# 2_SIM.net
KiCad netlist of a schematic drawn in Altium Designer
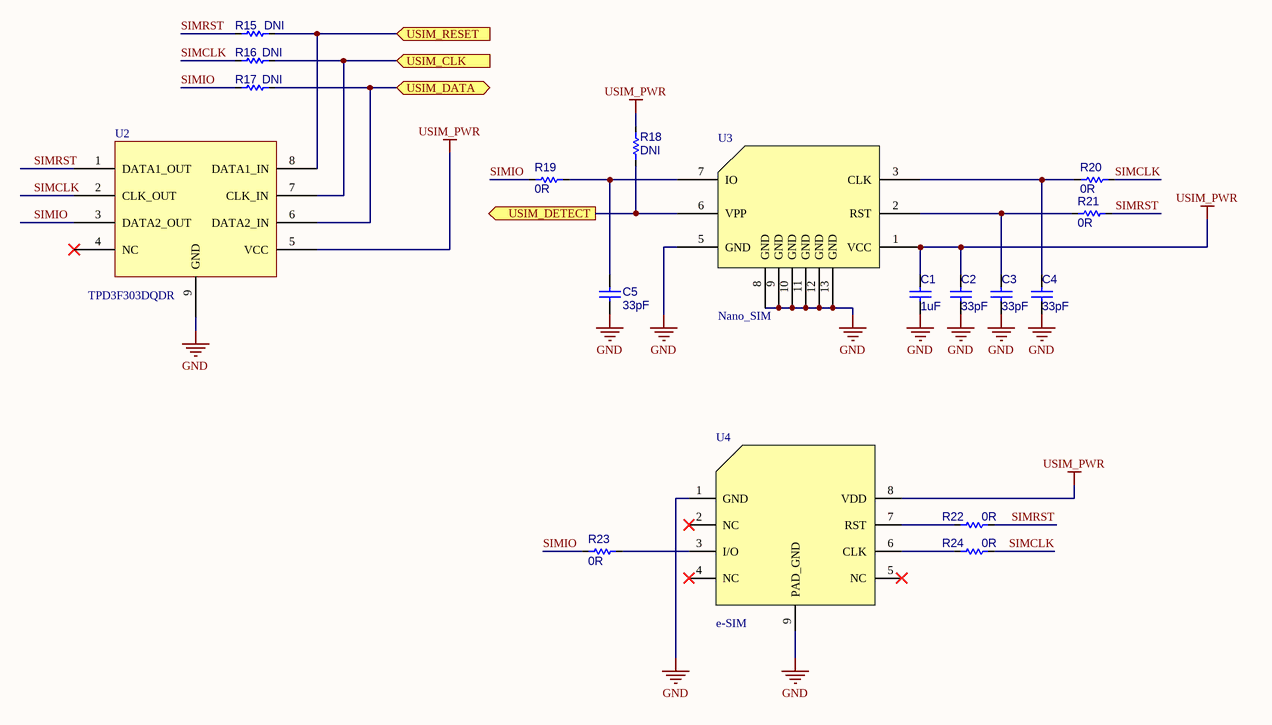
[diagram p0: 2.SIM.SchDoc]

(export (version "E")
  (design (tool "Eeschema 10.0.6"))
  (components
    (comp (ref "C1")
      (value "1uF")
      (footprint "CAP-0402")
      (description "Ceramic CAP 0402(1005)")
      (libsource (lib "Scott_lib") (part "CAP-0402"))
    )
    (comp (ref "C2")
      (value "33pF")
      (footprint "CAP-0402")
      (description "Ceramic CAP 0402(1005)")
      (libsource (lib "Scott_lib") (part "CAP-0402"))
    )
    (comp (ref "C3")
      (value "33pF")
      (footprint "CAP-0402")
      (description "Ceramic CAP 0402(1005)")
      (libsource (lib "Scott_lib") (part "CAP-0402"))
    )
    (comp (ref "C4")
      (value "33pF")
      (footprint "CAP-0402")
      (description "Ceramic CAP 0402(1005)")
      (libsource (lib "Scott_lib") (part "CAP-0402"))
    )
    (comp (ref "C5")
      (value "33pF")
      (footprint "CAP-0402")
      (description "Ceramic CAP 0402(1005)")
      (libsource (lib "Scott_lib") (part "CAP-0402"))
    )
    (comp (ref "R15")
      (value "DNI")
      (footprint "RES-0402")
      (description "RES-0402")
      (libsource (lib "Scott_lib") (part "RES-0402"))
    )
    (comp (ref "R16")
      (value "DNI")
      (footprint "RES-0402")
      (description "RES-0402")
      (libsource (lib "Scott_lib") (part "RES-0402"))
    )
    (comp (ref "R17")
      (value "DNI")
      (footprint "RES-0402")
      (description "RES-0402")
      (libsource (lib "Scott_lib") (part "RES-0402"))
    )
    (comp (ref "R18")
      (value "DNI")
      (footprint "RES-0402")
      (description "RES-0402")
      (libsource (lib "Scott_lib") (part "RES-0402"))
    )
    (comp (ref "R19")
      (value "0R")
      (footprint "RES-0402")
      (description "RES-0402")
      (libsource (lib "Scott_lib") (part "RES-0402"))
    )
    (comp (ref "R20")
      (value "0R")
      (footprint "RES-0402")
      (description "RES-0402")
      (libsource (lib "Scott_lib") (part "RES-0402"))
    )
    (comp (ref "R21")
      (value "0R")
      (footprint "RES-0402")
      (description "RES-0402")
      (libsource (lib "Scott_lib") (part "RES-0402"))
    )
    (comp (ref "R22")
      (value "0R")
      (footprint "RES-0402")
      (description "RES-0402")
      (libsource (lib "Scott_lib") (part "RES-0402"))
    )
    (comp (ref "R23")
      (value "0R")
      (footprint "RES-0402")
      (description "RES-0402")
      (libsource (lib "Scott_lib") (part "RES-0402"))
    )
    (comp (ref "R24")
      (value "0R")
      (footprint "RES-0402")
      (description "RES-0402")
      (libsource (lib "Scott_lib") (part "RES-0402"))
    )
    (comp (ref "U2")
      (value "TPD3F303DQDR")
      (footprint "PWSON08(0.4/1.45X1.8)")
      (description "ESD Protection SIM")
      (libsource (lib "Isaac_library") (part "TPD3F303DQDR"))
    )
    (comp (ref "U3")
      (value "Nano_SIM")
      (footprint "693-043-020-611")
      (description "Nano SIM SMT 1.2mm Push/Pull")
      (libsource (lib "Isaac_library") (part "Nano_SIM"))
    )
    (comp (ref "U4")
      (value "e-SIM")
      (footprint "e-SIM")
      (libsource (lib "WM-N400MSE_Starter_kit") (part "e-SIM"))
    )
  )
  (nets
    (net (code "1") (name "/SIMCLK") (class "Default")
      (node (ref "R16") (pin "2") (pinfunction "2_2") (pintype "passive"))
      (node (ref "R20") (pin "2") (pinfunction "2_2") (pintype "passive"))
      (node (ref "R24") (pin "2") (pinfunction "2_2") (pintype "passive"))
      (node (ref "U2") (pin "2") (pinfunction "CLK_OUT_2") (pintype "passive"))
    )
    (net (code "2") (name "/SIMIO") (class "Default")
      (node (ref "R17") (pin "2") (pinfunction "2_2") (pintype "passive"))
      (node (ref "R19") (pin "1") (pinfunction "1_1") (pintype "passive"))
      (node (ref "R23") (pin "1") (pinfunction "1_1") (pintype "passive"))
      (node (ref "U2") (pin "3") (pinfunction "DATA2_OUT_3") (pintype "passive"))
    )
    (net (code "3") (name "/SIMRST") (class "Default")
      (node (ref "R15") (pin "2") (pinfunction "2_2") (pintype "passive"))
      (node (ref "R21") (pin "2") (pinfunction "2_2") (pintype "passive"))
      (node (ref "R22") (pin "2") (pinfunction "2_2") (pintype "passive"))
      (node (ref "U2") (pin "1") (pinfunction "DATA1_OUT_1") (pintype "passive"))
    )
    (net (code "4") (name "/USIM_CLK") (class "Default")
      (node (ref "R16") (pin "1") (pinfunction "1_1") (pintype "passive"))
      (node (ref "U2") (pin "7") (pinfunction "CLK_IN_7") (pintype "passive"))
    )
    (net (code "5") (name "/USIM_DATA") (class "Default")
      (node (ref "R17") (pin "1") (pinfunction "1_1") (pintype "passive"))
      (node (ref "U2") (pin "6") (pinfunction "DATA2_IN_6") (pintype "passive"))
    )
    (net (code "6") (name "/USIM_DETECT") (class "Default")
      (node (ref "R18") (pin "2") (pinfunction "2_2") (pintype "passive"))
      (node (ref "U3") (pin "6") (pinfunction "VPP_6") (pintype "passive"))
    )
    (net (code "7") (name "/USIM_RESET") (class "Default")
      (node (ref "R15") (pin "1") (pinfunction "1_1") (pintype "passive"))
      (node (ref "U2") (pin "8") (pinfunction "DATA1_IN_8") (pintype "passive"))
    )
    (net (code "8") (name "GND") (class "Default")
      (node (ref "C1") (pin "1") (pinfunction "1_1") (pintype "passive"))
      (node (ref "C2") (pin "1") (pinfunction "1_1") (pintype "passive"))
      (node (ref "C3") (pin "1") (pinfunction "1_1") (pintype "passive"))
      (node (ref "C4") (pin "1") (pinfunction "1_1") (pintype "passive"))
      (node (ref "C5") (pin "1") (pinfunction "1_1") (pintype "passive"))
      (node (ref "U2") (pin "9") (pinfunction "GND_9") (pintype "passive"))
      (node (ref "U3") (pin "10") (pinfunction "GND_10") (pintype "passive"))
      (node (ref "U3") (pin "11") (pinfunction "GND_11") (pintype "passive"))
      (node (ref "U3") (pin "12") (pinfunction "GND_12") (pintype "passive"))
      (node (ref "U3") (pin "13") (pinfunction "GND_13") (pintype "passive"))
      (node (ref "U3") (pin "5") (pinfunction "GND_5") (pintype "passive"))
      (node (ref "U3") (pin "8") (pinfunction "GND_8") (pintype "passive"))
      (node (ref "U3") (pin "9") (pinfunction "GND_9") (pintype "passive"))
      (node (ref "U4") (pin "1") (pinfunction "GND_1") (pintype "passive"))
      (node (ref "U4") (pin "9") (pinfunction "PAD_GND_9") (pintype "passive"))
    )
    (net (code "9") (name "Net-(U3-CLK)") (class "Default")
      (node (ref "C4") (pin "2") (pinfunction "2_2") (pintype "passive"))
      (node (ref "R20") (pin "1") (pinfunction "1_1") (pintype "passive"))
      (node (ref "U3") (pin "3") (pinfunction "CLK_3") (pintype "passive"))
    )
    (net (code "10") (name "Net-(U3-IO)") (class "Default")
      (node (ref "C5") (pin "2") (pinfunction "2_2") (pintype "passive"))
      (node (ref "R19") (pin "2") (pinfunction "2_2") (pintype "passive"))
      (node (ref "U3") (pin "7") (pinfunction "IO_7") (pintype "passive"))
    )
    (net (code "11") (name "Net-(U3-RST)") (class "Default")
      (node (ref "C3") (pin "2") (pinfunction "2_2") (pintype "passive"))
      (node (ref "R21") (pin "1") (pinfunction "1_1") (pintype "passive"))
      (node (ref "U3") (pin "2") (pinfunction "RST_2") (pintype "passive"))
    )
    (net (code "12") (name "Net-(U4-CLK)") (class "Default")
      (node (ref "R24") (pin "1") (pinfunction "1_1") (pintype "passive"))
      (node (ref "U4") (pin "6") (pinfunction "CLK_6") (pintype "passive"))
    )
    (net (code "13") (name "Net-(U4-I{slash}O)") (class "Default")
      (node (ref "R23") (pin "2") (pinfunction "2_2") (pintype "passive"))
      (node (ref "U4") (pin "3") (pinfunction "I/O_3") (pintype "passive"))
    )
    (net (code "14") (name "Net-(U4-RST)") (class "Default")
      (node (ref "R22") (pin "1") (pinfunction "1_1") (pintype "passive"))
      (node (ref "U4") (pin "7") (pinfunction "RST_7") (pintype "passive"))
    )
    (net (code "15") (name "USIM_PWR") (class "Default")
      (node (ref "C1") (pin "2") (pinfunction "2_2") (pintype "passive"))
      (node (ref "C2") (pin "2") (pinfunction "2_2") (pintype "passive"))
      (node (ref "R18") (pin "1") (pinfunction "1_1") (pintype "passive"))
      (node (ref "U2") (pin "5") (pinfunction "VCC_5") (pintype "passive"))
      (node (ref "U3") (pin "1") (pinfunction "VCC_1") (pintype "passive"))
      (node (ref "U4") (pin "8") (pinfunction "VDD_8") (pintype "passive"))
    )
    (net (code "16") (name "unconnected-(U2-NC-Pad4)") (class "Default")
      (node (ref "U2") (pin "4") (pinfunction "NC_4") (pintype "passive+no_connect"))
    )
    (net (code "17") (name "unconnected-(U4-NC-Pad2)") (class "Default")
      (node (ref "U4") (pin "2") (pinfunction "NC_2") (pintype "passive+no_connect"))
    )
    (net (code "18") (name "unconnected-(U4-NC-Pad4)") (class "Default")
      (node (ref "U4") (pin "4") (pinfunction "NC_4") (pintype "passive+no_connect"))
    )
    (net (code "19") (name "unconnected-(U4-NC-Pad5)") (class "Default")
      (node (ref "U4") (pin "5") (pinfunction "NC_5") (pintype "passive+no_connect"))
    )
  )
)
